# vsBenchPowerSupply.net
KiCad netlist of a schematic drawn in EAGLE
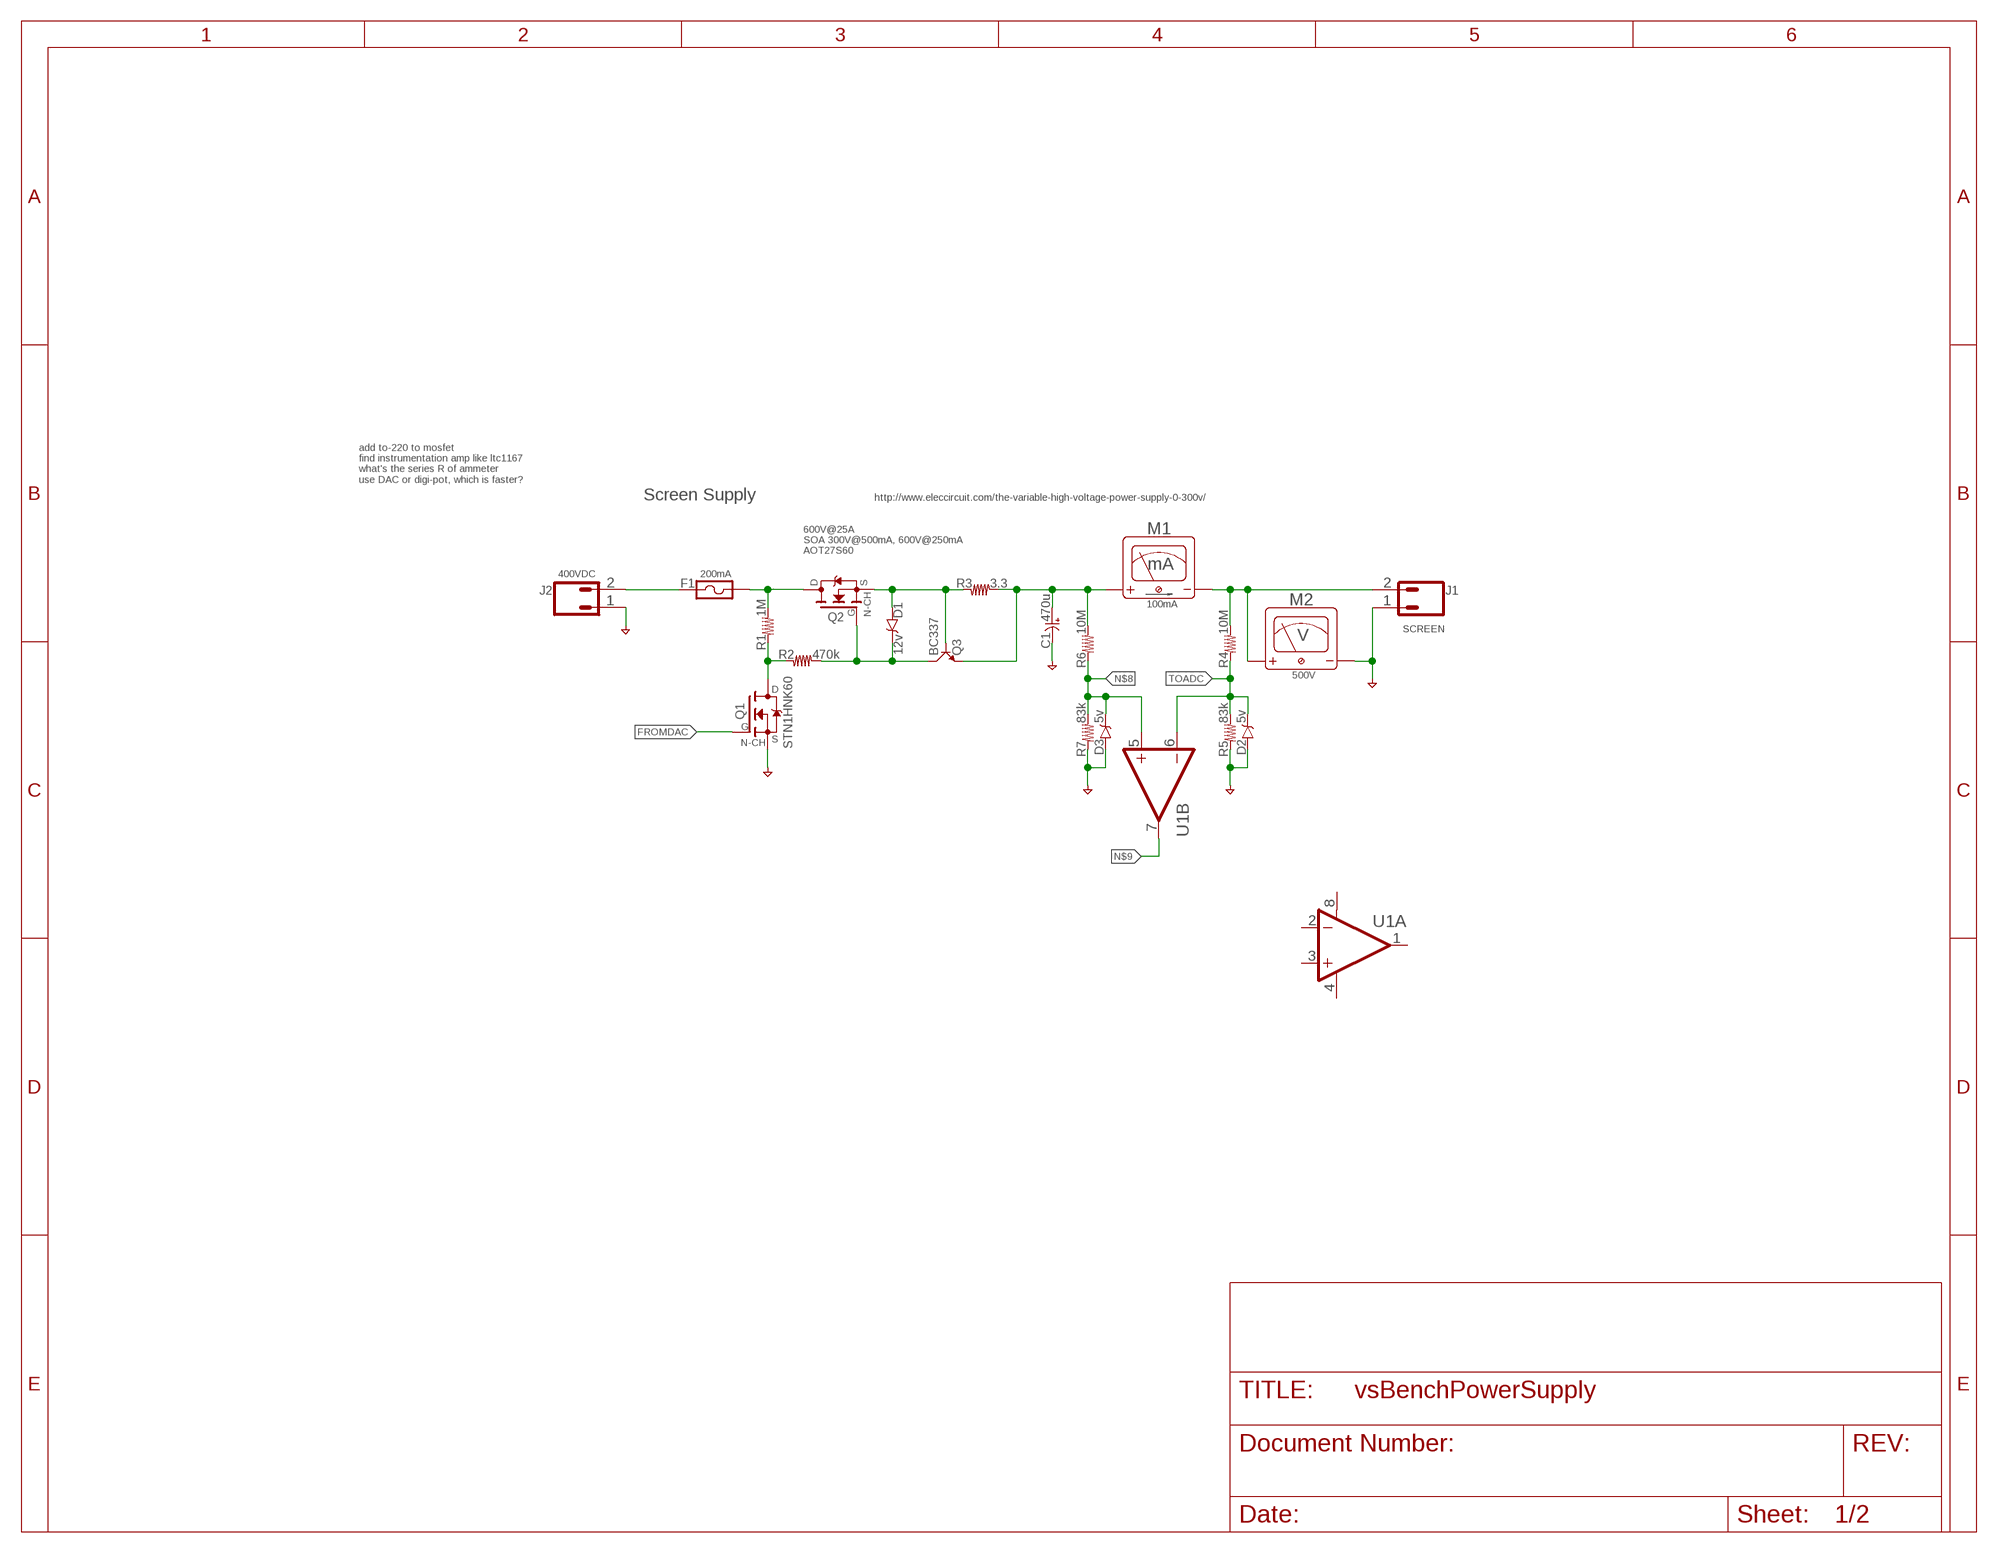
[diagram p0: schematic, sheet 1]
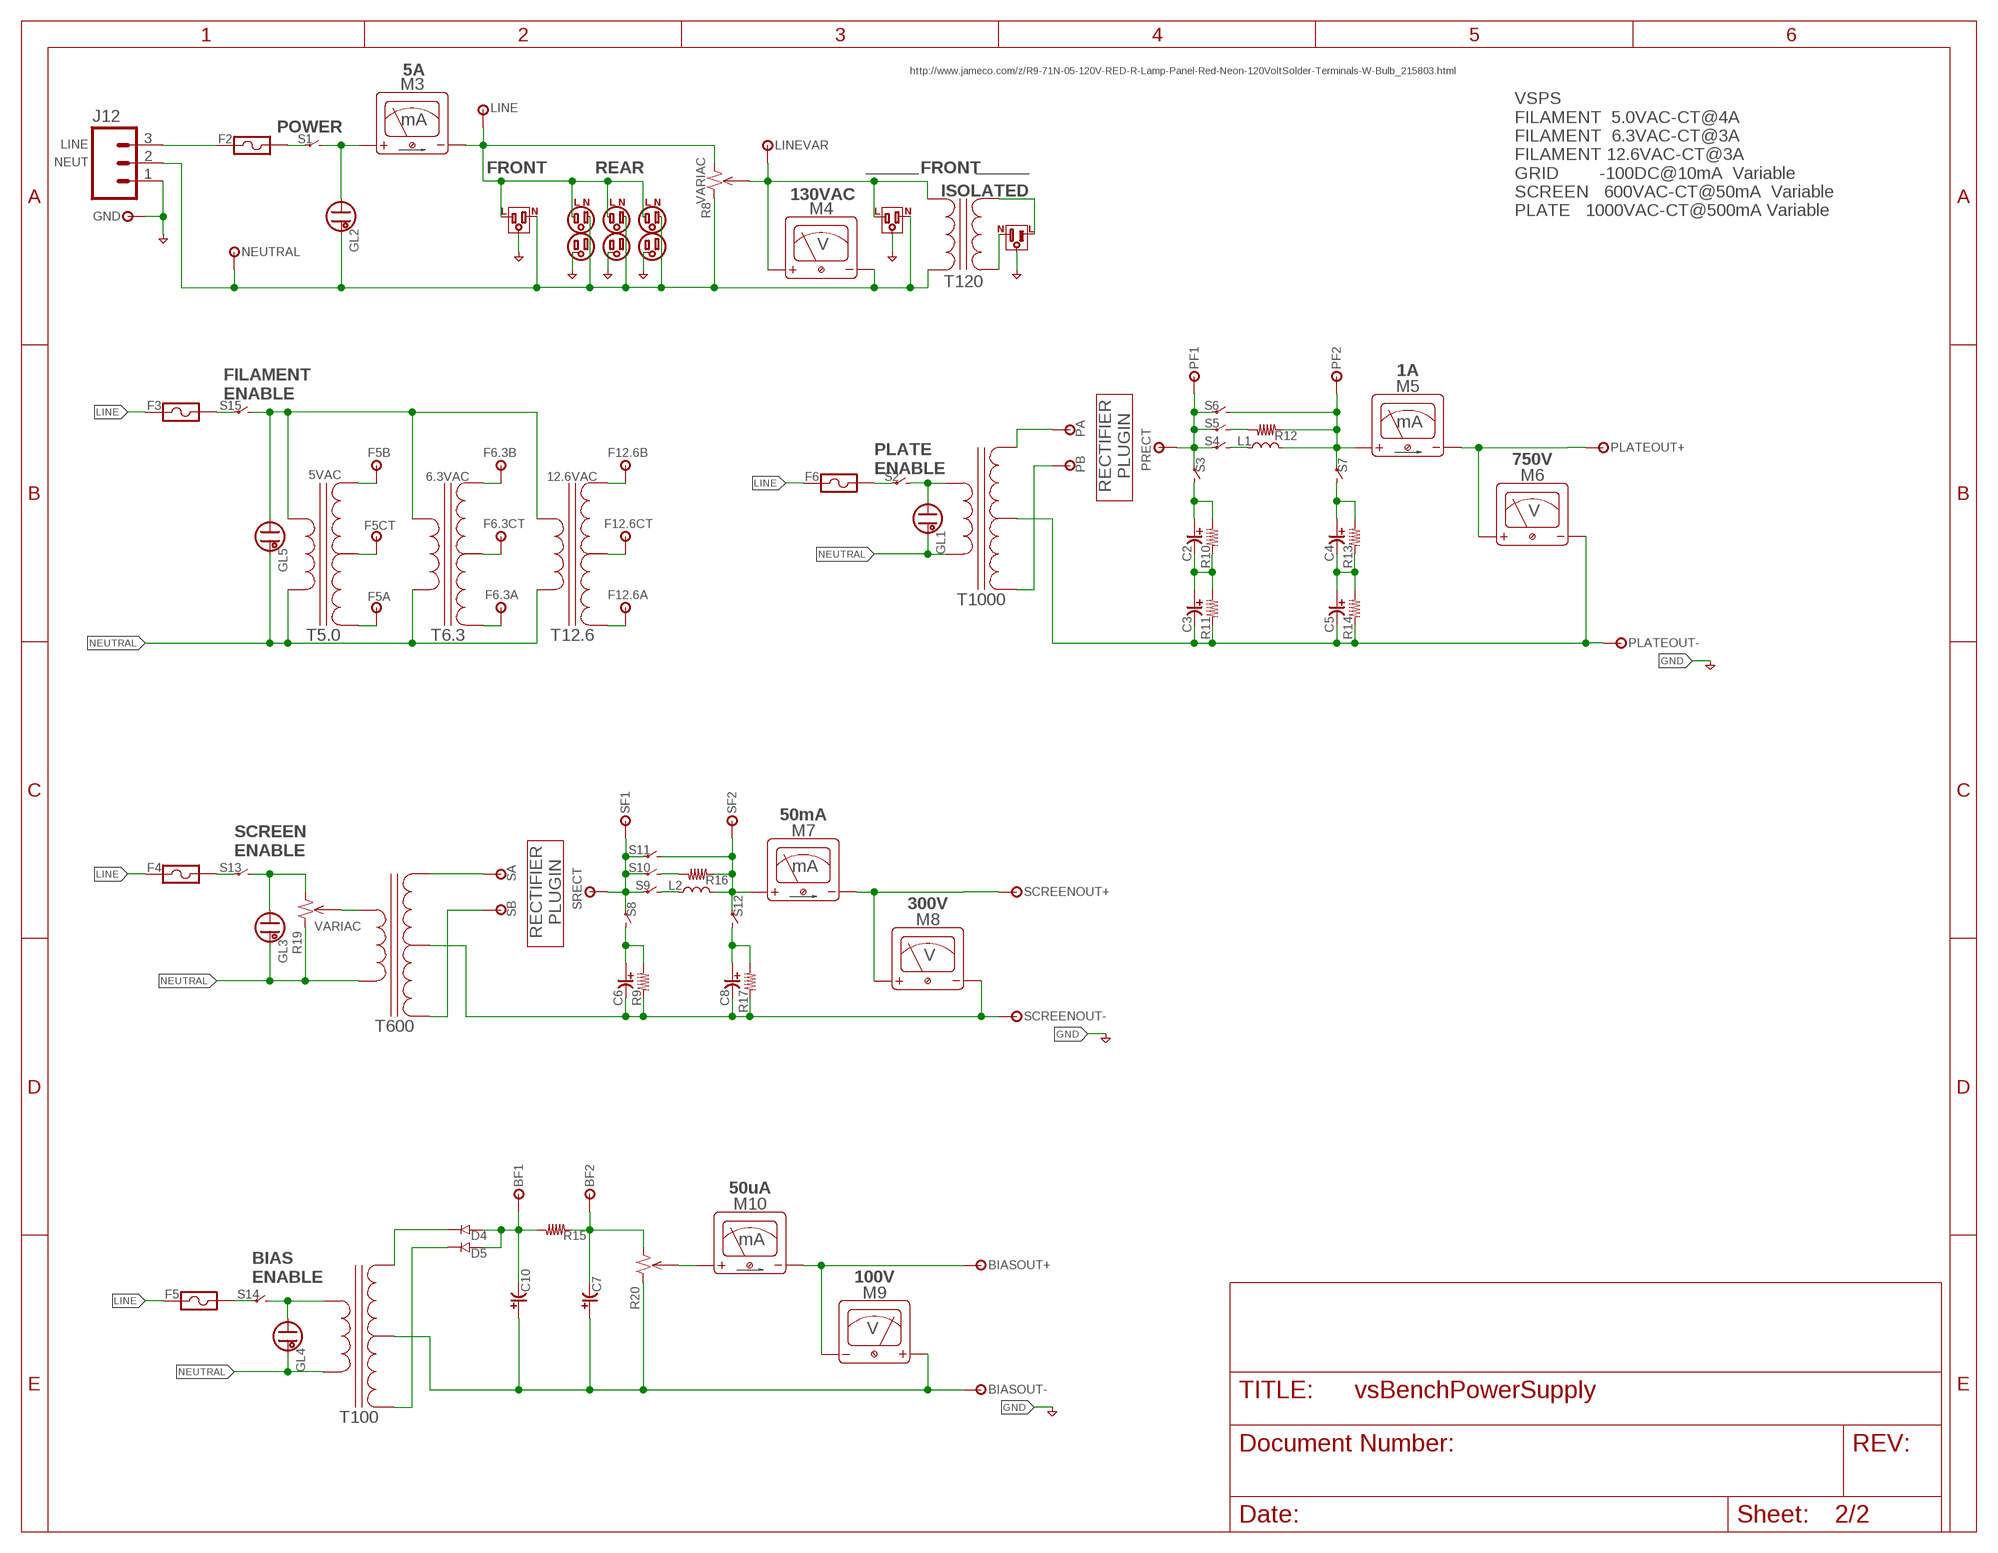
[diagram p1: schematic, sheet 2]

(export (version "E")
  (design (tool "Eeschema 10.0.6"))
  (components
    (comp (ref "C1")
      (value "470u")
      (footprint "eagle-import:E5-10,5")
      (libsource (lib "eagle-import") (part "C-E5-10.5"))
    )
    (comp (ref "D1")
      (value "12v")
      (footprint "eagle-import:SOD-323")
      (libsource (lib "eagle-import") (part "DIODE-ZENER-0805"))
    )
    (comp (ref "D2")
      (value "5v")
      (footprint "eagle-import:SOD-323")
      (libsource (lib "eagle-import") (part "DIODE-ZENER-0805"))
    )
    (comp (ref "D3")
      (value "5v")
      (footprint "eagle-import:SOD-323")
      (libsource (lib "eagle-import") (part "DIODE-ZENER-0805"))
    )
    (comp (ref "F1")
      (value "FUSE-HOLDER-3557-2")
      (footprint "eagle-import:3557-2")
      (libsource (lib "eagle-import") (part "FUSE-HOLDER-3557-2"))
    )
    (comp (ref "J1")
      (value "CONN-02-3.81MM-PLUGIN-SCREW")
      (footprint "eagle-import:CONN-3.81MM-KF2EDG-2")
      (libsource (lib "eagle-import") (part "CONN-02-3.81MM-PLUGIN-SCREW"))
    )
    (comp (ref "J2")
      (value "CONN-02-3.81MM-PLUGIN-SCREW")
      (footprint "eagle-import:CONN-3.81MM-KF2EDG-2")
      (libsource (lib "eagle-import") (part "CONN-02-3.81MM-PLUGIN-SCREW"))
    )
    (comp (ref "M1")
      (value "METER-PANEL-ANALOG-CURRENT-PLUGIN-3.81MM")
      (footprint "eagle-import:CONN-3.81MM-KF2EDG-2")
      (libsource (lib "eagle-import") (part "METER-PANEL-ANALOG-CURRENT-PLUGIN-3.81MM"))
    )
    (comp (ref "M2")
      (value "METER-PANEL-ANALOG-VOLTAGE-PLUGIN-3.81MM")
      (footprint "eagle-import:CONN-3.81MM-KF2EDG-2")
      (libsource (lib "eagle-import") (part "METER-PANEL-ANALOG-VOLTAGE-PLUGIN-3.81MM"))
    )
    (comp (ref "Q1")
      (value "STN1HNK60")
      (footprint "eagle-import:SOT23-3")
      (libsource (lib "eagle-import") (part "FET-NCH-SOT23"))
    )
    (comp (ref "Q2")
      (value "FET-NCH-TO252")
      (footprint "eagle-import:TO252")
      (libsource (lib "eagle-import") (part "FET-NCH-TO252"))
    )
    (comp (ref "Q3")
      (value "BC337")
      (footprint "eagle-import:SOT23-3")
      (libsource (lib "eagle-import") (part "TRANSISTOR_NPNSOT23-3"))
    )
    (comp (ref "R1")
      (value "1M")
      (footprint "eagle-import:R2512")
      (fields (field (name "DESC") "1W"))
      (libsource (lib "eagle-import") (part "R-2512"))
    )
    (comp (ref "R2")
      (value "470k")
      (footprint "eagle-import:R2512")
      (libsource (lib "eagle-import") (part "R-2512"))
    )
    (comp (ref "R3")
      (value "3.3")
      (footprint "eagle-import:R2512")
      (libsource (lib "eagle-import") (part "R-2512"))
    )
    (comp (ref "R4")
      (value "10M")
      (footprint "eagle-import:R2512")
      (fields (field (name "DESC") ".1%"))
      (libsource (lib "eagle-import") (part "R-2512"))
    )
    (comp (ref "R5")
      (value "83k")
      (footprint "eagle-import:R2512")
      (fields (field (name "DESC") ".1%"))
      (libsource (lib "eagle-import") (part "R-2512"))
    )
    (comp (ref "R6")
      (value "10M")
      (footprint "eagle-import:R2512")
      (fields (field (name "DESC") ",1%"))
      (libsource (lib "eagle-import") (part "R-2512"))
    )
    (comp (ref "R7")
      (value "83k")
      (footprint "eagle-import:R2512")
      (fields (field (name "DESC") ".1%"))
      (libsource (lib "eagle-import") (part "R-2512"))
    )
    (comp (ref "U1")
      (value "AMP-OPAMP-DUAL-SO08")
      (footprint "eagle-import:SO08")
      (libsource (lib "eagle-import") (part "AMP-OPAMP-DUAL-SO08"))
    )
    (comp (ref "BF1")
      (value "TESTPOINTTHRU")
      (footprint "eagle-import:TPTHRU")
      (libsource (lib "eagle-import") (part "TESTPOINTTHRU"))
    )
    (comp (ref "BF2")
      (value "TESTPOINTTHRU")
      (footprint "eagle-import:TPTHRU")
      (libsource (lib "eagle-import") (part "TESTPOINTTHRU"))
    )
    (comp (ref "BIASOUT+")
      (value "TESTPOINTTHRU")
      (footprint "eagle-import:TPTHRU")
      (libsource (lib "eagle-import") (part "TESTPOINTTHRU"))
    )
    (comp (ref "BIASOUT-")
      (value "TESTPOINTTHRU")
      (footprint "eagle-import:TPTHRU")
      (libsource (lib "eagle-import") (part "TESTPOINTTHRU"))
    )
    (comp (ref "C2")
      (value "C-POLARIZED-SMD-E-3MM")
      (footprint "eagle-import:E-3")
      (libsource (lib "eagle-import") (part "C-POLARIZED-SMD-E-3MM"))
    )
    (comp (ref "C3")
      (value "C-POLARIZED-SMD-E-3MM")
      (footprint "eagle-import:E-3")
      (libsource (lib "eagle-import") (part "C-POLARIZED-SMD-E-3MM"))
    )
    (comp (ref "C4")
      (value "C-POLARIZED-SMD-E-3MM")
      (footprint "eagle-import:E-3")
      (libsource (lib "eagle-import") (part "C-POLARIZED-SMD-E-3MM"))
    )
    (comp (ref "C5")
      (value "C-POLARIZED-SMD-E-3MM")
      (footprint "eagle-import:E-3")
      (libsource (lib "eagle-import") (part "C-POLARIZED-SMD-E-3MM"))
    )
    (comp (ref "C6")
      (value "C-POLARIZED-SMD-E-3MM")
      (footprint "eagle-import:E-3")
      (libsource (lib "eagle-import") (part "C-POLARIZED-SMD-E-3MM"))
    )
    (comp (ref "C7")
      (value "C-POLARIZED-SMD-E-3MM")
      (footprint "eagle-import:E-3")
      (libsource (lib "eagle-import") (part "C-POLARIZED-SMD-E-3MM"))
    )
    (comp (ref "C8")
      (value "C-POLARIZED-SMD-E-3MM")
      (footprint "eagle-import:E-3")
      (libsource (lib "eagle-import") (part "C-POLARIZED-SMD-E-3MM"))
    )
    (comp (ref "C10")
      (value "C-POLARIZED-SMD-E-3MM")
      (footprint "eagle-import:E-3")
      (libsource (lib "eagle-import") (part "C-POLARIZED-SMD-E-3MM"))
    )
    (comp (ref "D4")
      (value "DIODE-1N4148")
      (footprint "eagle-import:DO-35")
      (libsource (lib "eagle-import") (part "DIODE-1N4148"))
    )
    (comp (ref "D5")
      (value "DIODE-1N4148")
      (footprint "eagle-import:DO-35")
      (libsource (lib "eagle-import") (part "DIODE-1N4148"))
    )
    (comp (ref "F2")
      (value "FUSE-HOLDER-3557-2")
      (footprint "eagle-import:3557-2")
      (libsource (lib "eagle-import") (part "FUSE-HOLDER-3557-2"))
    )
    (comp (ref "F3")
      (value "FUSE-HOLDER-3557-2")
      (footprint "eagle-import:3557-2")
      (libsource (lib "eagle-import") (part "FUSE-HOLDER-3557-2"))
    )
    (comp (ref "F4")
      (value "FUSE-HOLDER-3557-2")
      (footprint "eagle-import:3557-2")
      (libsource (lib "eagle-import") (part "FUSE-HOLDER-3557-2"))
    )
    (comp (ref "F5")
      (value "FUSE-HOLDER-3557-2")
      (footprint "eagle-import:3557-2")
      (libsource (lib "eagle-import") (part "FUSE-HOLDER-3557-2"))
    )
    (comp (ref "F5A")
      (value "TESTPOINTTHRU")
      (footprint "eagle-import:TPTHRU")
      (libsource (lib "eagle-import") (part "TESTPOINTTHRU"))
    )
    (comp (ref "F5B")
      (value "TESTPOINTTHRU")
      (footprint "eagle-import:TPTHRU")
      (libsource (lib "eagle-import") (part "TESTPOINTTHRU"))
    )
    (comp (ref "F5CT")
      (value "TESTPOINTTHRU")
      (footprint "eagle-import:TPTHRU")
      (libsource (lib "eagle-import") (part "TESTPOINTTHRU"))
    )
    (comp (ref "F6")
      (value "FUSE-HOLDER-3557-2")
      (footprint "eagle-import:3557-2")
      (libsource (lib "eagle-import") (part "FUSE-HOLDER-3557-2"))
    )
    (comp (ref "F6.3A")
      (value "TESTPOINTTHRU")
      (footprint "eagle-import:TPTHRU")
      (libsource (lib "eagle-import") (part "TESTPOINTTHRU"))
    )
    (comp (ref "F6.3B")
      (value "TESTPOINTTHRU")
      (footprint "eagle-import:TPTHRU")
      (libsource (lib "eagle-import") (part "TESTPOINTTHRU"))
    )
    (comp (ref "F6.3CT")
      (value "TESTPOINTTHRU")
      (footprint "eagle-import:TPTHRU")
      (libsource (lib "eagle-import") (part "TESTPOINTTHRU"))
    )
    (comp (ref "F12.6A")
      (value "TESTPOINTTHRU")
      (footprint "eagle-import:TPTHRU")
      (libsource (lib "eagle-import") (part "TESTPOINTTHRU"))
    )
    (comp (ref "F12.6B")
      (value "TESTPOINTTHRU")
      (footprint "eagle-import:TPTHRU")
      (libsource (lib "eagle-import") (part "TESTPOINTTHRU"))
    )
    (comp (ref "F12.6CT")
      (value "TESTPOINTTHRU")
      (footprint "eagle-import:TPTHRU")
      (libsource (lib "eagle-import") (part "TESTPOINTTHRU"))
    )
    (comp (ref "GL1")
      (value "INDICATOR-NEON-BULB-NE2-DRILL")
      (footprint "eagle-import:NE2-NEON-BULB-DRILL")
      (libsource (lib "eagle-import") (part "INDICATOR-NEON-BULB-NE2-DRILL"))
    )
    (comp (ref "GL2")
      (value "INDICATOR-NEON-BULB-NE2-DRILL")
      (footprint "eagle-import:NE2-NEON-BULB-DRILL")
      (libsource (lib "eagle-import") (part "INDICATOR-NEON-BULB-NE2-DRILL"))
    )
    (comp (ref "GL3")
      (value "INDICATOR-NEON-BULB-NE2-DRILL")
      (footprint "eagle-import:NE2-NEON-BULB-DRILL")
      (libsource (lib "eagle-import") (part "INDICATOR-NEON-BULB-NE2-DRILL"))
    )
    (comp (ref "GL4")
      (value "INDICATOR-NEON-BULB-NE2-DRILL")
      (footprint "eagle-import:NE2-NEON-BULB-DRILL")
      (libsource (lib "eagle-import") (part "INDICATOR-NEON-BULB-NE2-DRILL"))
    )
    (comp (ref "GL5")
      (value "INDICATOR-NEON-BULB-NE2-DRILL")
      (footprint "eagle-import:NE2-NEON-BULB-DRILL")
      (libsource (lib "eagle-import") (part "INDICATOR-NEON-BULB-NE2-DRILL"))
    )
    (comp (ref "GND")
      (value "TESTPOINTTHRU")
      (footprint "eagle-import:TPTHRU")
      (libsource (lib "eagle-import") (part "TESTPOINTTHRU"))
    )
    (comp (ref "J3")
      (value "OUTLET-RECEPTABLE-SINGLE")
      (footprint "eagle-import:CONN-3.81MM-KF2EDG-3")
      (libsource (lib "eagle-import") (part "OUTLET-RECEPTABLE-SINGLE"))
    )
    (comp (ref "J4")
      (value "OUTLET-RECEPTABLE-SINGLE")
      (footprint "eagle-import:CONN-3.81MM-KF2EDG-3")
      (libsource (lib "eagle-import") (part "OUTLET-RECEPTABLE-SINGLE"))
    )
    (comp (ref "J5")
      (value "OUTLET-RECEPTABLE-SINGLE")
      (footprint "eagle-import:CONN-3.81MM-KF2EDG-3")
      (libsource (lib "eagle-import") (part "OUTLET-RECEPTABLE-SINGLE"))
    )
    (comp (ref "J12")
      (value "CONN-03-3.81MM-PLUGIN-SCREW")
      (footprint "eagle-import:CONN-3.81MM-KF2EDG-3")
      (libsource (lib "eagle-import") (part "CONN-03-3.81MM-PLUGIN-SCREW"))
    )
    (comp (ref "L1")
      (value "INDUCTOR-0805")
      (footprint "eagle-import:R0805")
      (libsource (lib "eagle-import") (part "INDUCTOR-0805"))
    )
    (comp (ref "L2")
      (value "INDUCTOR-0805")
      (footprint "eagle-import:R0805")
      (libsource (lib "eagle-import") (part "INDUCTOR-0805"))
    )
    (comp (ref "LINE")
      (value "TESTPOINTTHRU")
      (footprint "eagle-import:TPTHRU")
      (libsource (lib "eagle-import") (part "TESTPOINTTHRU"))
    )
    (comp (ref "LINEVAR")
      (value "TESTPOINTTHRU")
      (footprint "eagle-import:TPTHRU")
      (libsource (lib "eagle-import") (part "TESTPOINTTHRU"))
    )
    (comp (ref "M3")
      (value "METER-PANEL-ANALOG-CURRENT-PLUGIN-3.81MM")
      (footprint "eagle-import:CONN-3.81MM-KF2EDG-2")
      (libsource (lib "eagle-import") (part "METER-PANEL-ANALOG-CURRENT-PLUGIN-3.81MM"))
    )
    (comp (ref "M4")
      (value "METER-PANEL-ANALOG-VOLTAGE-PLUGIN-3.81MM")
      (footprint "eagle-import:CONN-3.81MM-KF2EDG-2")
      (libsource (lib "eagle-import") (part "METER-PANEL-ANALOG-VOLTAGE-PLUGIN-3.81MM"))
    )
    (comp (ref "M5")
      (value "METER-PANEL-ANALOG-CURRENT-PLUGIN-3.81MM")
      (footprint "eagle-import:CONN-3.81MM-KF2EDG-2")
      (libsource (lib "eagle-import") (part "METER-PANEL-ANALOG-CURRENT-PLUGIN-3.81MM"))
    )
    (comp (ref "M6")
      (value "METER-PANEL-ANALOG-VOLTAGE-PLUGIN-3.81MM")
      (footprint "eagle-import:CONN-3.81MM-KF2EDG-2")
      (libsource (lib "eagle-import") (part "METER-PANEL-ANALOG-VOLTAGE-PLUGIN-3.81MM"))
    )
    (comp (ref "M7")
      (value "METER-PANEL-ANALOG-CURRENT-PLUGIN-3.81MM")
      (footprint "eagle-import:CONN-3.81MM-KF2EDG-2")
      (libsource (lib "eagle-import") (part "METER-PANEL-ANALOG-CURRENT-PLUGIN-3.81MM"))
    )
    (comp (ref "M8")
      (value "METER-PANEL-ANALOG-VOLTAGE-PLUGIN-3.81MM")
      (footprint "eagle-import:CONN-3.81MM-KF2EDG-2")
      (libsource (lib "eagle-import") (part "METER-PANEL-ANALOG-VOLTAGE-PLUGIN-3.81MM"))
    )
    (comp (ref "M9")
      (value "METER-PANEL-ANALOG-VOLTAGE-PLUGIN-3.81MM")
      (footprint "eagle-import:CONN-3.81MM-KF2EDG-2")
      (libsource (lib "eagle-import") (part "METER-PANEL-ANALOG-VOLTAGE-PLUGIN-3.81MM"))
    )
    (comp (ref "M10")
      (value "METER-PANEL-ANALOG-CURRENT-PLUGIN-3.81MM")
      (footprint "eagle-import:CONN-3.81MM-KF2EDG-2")
      (libsource (lib "eagle-import") (part "METER-PANEL-ANALOG-CURRENT-PLUGIN-3.81MM"))
    )
    (comp (ref "NEUTRAL")
      (value "TESTPOINTTHRU")
      (footprint "eagle-import:TPTHRU")
      (libsource (lib "eagle-import") (part "TESTPOINTTHRU"))
    )
    (comp (ref "PA")
      (value "TESTPOINTTHRU")
      (footprint "eagle-import:TPTHRU")
      (libsource (lib "eagle-import") (part "TESTPOINTTHRU"))
    )
    (comp (ref "PB")
      (value "TESTPOINTTHRU")
      (footprint "eagle-import:TPTHRU")
      (libsource (lib "eagle-import") (part "TESTPOINTTHRU"))
    )
    (comp (ref "PF1")
      (value "TESTPOINTTHRU")
      (footprint "eagle-import:TPTHRU")
      (libsource (lib "eagle-import") (part "TESTPOINTTHRU"))
    )
    (comp (ref "PF2")
      (value "TESTPOINTTHRU")
      (footprint "eagle-import:TPTHRU")
      (libsource (lib "eagle-import") (part "TESTPOINTTHRU"))
    )
    (comp (ref "PLATEOUT+")
      (value "TESTPOINTTHRU")
      (footprint "eagle-import:TPTHRU")
      (libsource (lib "eagle-import") (part "TESTPOINTTHRU"))
    )
    (comp (ref "PLATEOUT-")
      (value "TESTPOINTTHRU")
      (footprint "eagle-import:TPTHRU")
      (libsource (lib "eagle-import") (part "TESTPOINTTHRU"))
    )
    (comp (ref "PRECT")
      (value "TESTPOINTTHRU")
      (footprint "eagle-import:TPTHRU")
      (libsource (lib "eagle-import") (part "TESTPOINTTHRU"))
    )
    (comp (ref "R8")
      (value "POTENTIOMETER")
      (footprint "eagle-import:CONN-.100-3")
      (libsource (lib "eagle-import") (part "POTENTIOMETER"))
    )
    (comp (ref "R9")
      (value "R-0402")
      (footprint "eagle-import:R0402")
      (libsource (lib "eagle-import") (part "R-0402"))
    )
    (comp (ref "R10")
      (value "R-0402")
      (footprint "eagle-import:R0402")
      (libsource (lib "eagle-import") (part "R-0402"))
    )
    (comp (ref "R11")
      (value "R-0402")
      (footprint "eagle-import:R0402")
      (libsource (lib "eagle-import") (part "R-0402"))
    )
    (comp (ref "R12")
      (value "R-0402")
      (footprint "eagle-import:R0402")
      (libsource (lib "eagle-import") (part "R-0402"))
    )
    (comp (ref "R13")
      (value "R-0402")
      (footprint "eagle-import:R0402")
      (libsource (lib "eagle-import") (part "R-0402"))
    )
    (comp (ref "R14")
      (value "R-0402")
      (footprint "eagle-import:R0402")
      (libsource (lib "eagle-import") (part "R-0402"))
    )
    (comp (ref "R15")
      (value "R-0402")
      (footprint "eagle-import:R0402")
      (libsource (lib "eagle-import") (part "R-0402"))
    )
    (comp (ref "R16")
      (value "R-0402")
      (footprint "eagle-import:R0402")
      (libsource (lib "eagle-import") (part "R-0402"))
    )
    (comp (ref "R17")
      (value "R-0402")
      (footprint "eagle-import:R0402")
      (libsource (lib "eagle-import") (part "R-0402"))
    )
    (comp (ref "R19")
      (value "POTENTIOMETER")
      (footprint "eagle-import:CONN-.100-3")
      (libsource (lib "eagle-import") (part "POTENTIOMETER"))
    )
    (comp (ref "R20")
      (value "POTENTIOMETER")
      (footprint "eagle-import:CONN-.100-3")
      (libsource (lib "eagle-import") (part "POTENTIOMETER"))
    )
    (comp (ref "S1")
      (value "SWITCH-PANEL-SPST")
      (footprint "eagle-import:CONN-.100-2")
      (libsource (lib "eagle-import") (part "SWITCH-PANEL-SPST"))
    )
    (comp (ref "S2")
      (value "SWITCH-PANEL-SPST")
      (footprint "eagle-import:CONN-.100-2")
      (libsource (lib "eagle-import") (part "SWITCH-PANEL-SPST"))
    )
    (comp (ref "S3")
      (value "SWITCH-PANEL-SPST")
      (footprint "eagle-import:CONN-.100-2")
      (libsource (lib "eagle-import") (part "SWITCH-PANEL-SPST"))
    )
    (comp (ref "S4")
      (value "SWITCH-PANEL-SPST")
      (footprint "eagle-import:CONN-.100-2")
      (libsource (lib "eagle-import") (part "SWITCH-PANEL-SPST"))
    )
    (comp (ref "S5")
      (value "SWITCH-PANEL-SPST")
      (footprint "eagle-import:CONN-.100-2")
      (libsource (lib "eagle-import") (part "SWITCH-PANEL-SPST"))
    )
    (comp (ref "S6")
      (value "SWITCH-PANEL-SPST")
      (footprint "eagle-import:CONN-.100-2")
      (libsource (lib "eagle-import") (part "SWITCH-PANEL-SPST"))
    )
    (comp (ref "S7")
      (value "SWITCH-PANEL-SPST")
      (footprint "eagle-import:CONN-.100-2")
      (libsource (lib "eagle-import") (part "SWITCH-PANEL-SPST"))
    )
    (comp (ref "S8")
      (value "SWITCH-PANEL-SPST")
      (footprint "eagle-import:CONN-.100-2")
      (libsource (lib "eagle-import") (part "SWITCH-PANEL-SPST"))
    )
    (comp (ref "S9")
      (value "SWITCH-PANEL-SPST")
      (footprint "eagle-import:CONN-.100-2")
      (libsource (lib "eagle-import") (part "SWITCH-PANEL-SPST"))
    )
    (comp (ref "S10")
      (value "SWITCH-PANEL-SPST")
      (footprint "eagle-import:CONN-.100-2")
      (libsource (lib "eagle-import") (part "SWITCH-PANEL-SPST"))
    )
    (comp (ref "S11")
      (value "SWITCH-PANEL-SPST")
      (footprint "eagle-import:CONN-.100-2")
      (libsource (lib "eagle-import") (part "SWITCH-PANEL-SPST"))
    )
    (comp (ref "S12")
      (value "SWITCH-PANEL-SPST")
      (footprint "eagle-import:CONN-.100-2")
      (libsource (lib "eagle-import") (part "SWITCH-PANEL-SPST"))
    )
    (comp (ref "S13")
      (value "SWITCH-PANEL-SPST")
      (footprint "eagle-import:CONN-.100-2")
      (libsource (lib "eagle-import") (part "SWITCH-PANEL-SPST"))
    )
    (comp (ref "S14")
      (value "SWITCH-PANEL-SPST")
      (footprint "eagle-import:CONN-.100-2")
      (libsource (lib "eagle-import") (part "SWITCH-PANEL-SPST"))
    )
    (comp (ref "S15")
      (value "SWITCH-PANEL-SPST")
      (footprint "eagle-import:CONN-.100-2")
      (libsource (lib "eagle-import") (part "SWITCH-PANEL-SPST"))
    )
    (comp (ref "SA")
      (value "TESTPOINTTHRU")
      (footprint "eagle-import:TPTHRU")
      (libsource (lib "eagle-import") (part "TESTPOINTTHRU"))
    )
    (comp (ref "SB")
      (value "TESTPOINTTHRU")
      (footprint "eagle-import:TPTHRU")
      (libsource (lib "eagle-import") (part "TESTPOINTTHRU"))
    )
    (comp (ref "SCREENOUT+")
      (value "TESTPOINTTHRU")
      (footprint "eagle-import:TPTHRU")
      (libsource (lib "eagle-import") (part "TESTPOINTTHRU"))
    )
    (comp (ref "SCREENOUT-")
      (value "TESTPOINTTHRU")
      (footprint "eagle-import:TPTHRU")
      (libsource (lib "eagle-import") (part "TESTPOINTTHRU"))
    )
    (comp (ref "SF1")
      (value "TESTPOINTTHRU")
      (footprint "eagle-import:TPTHRU")
      (libsource (lib "eagle-import") (part "TESTPOINTTHRU"))
    )
    (comp (ref "SF2")
      (value "TESTPOINTTHRU")
      (footprint "eagle-import:TPTHRU")
      (libsource (lib "eagle-import") (part "TESTPOINTTHRU"))
    )
    (comp (ref "SRECT")
      (value "TESTPOINTTHRU")
      (footprint "eagle-import:TPTHRU")
      (libsource (lib "eagle-import") (part "TESTPOINTTHRU"))
    )
    (comp (ref "T5.0")
      (value "TRANSFORMER-3-2")
      (footprint "eagle-import:CONN-.100-5")
      (libsource (lib "eagle-import") (part "TRANSFORMER-3-2"))
    )
    (comp (ref "T6.3")
      (value "TRANSFORMER-3-2")
      (footprint "eagle-import:CONN-.100-5")
      (libsource (lib "eagle-import") (part "TRANSFORMER-3-2"))
    )
    (comp (ref "T12.6")
      (value "TRANSFORMER-3-2")
      (footprint "eagle-import:CONN-.100-5")
      (libsource (lib "eagle-import") (part "TRANSFORMER-3-2"))
    )
    (comp (ref "T100")
      (value "TRANSFORMER-3-2")
      (footprint "eagle-import:CONN-.100-5")
      (libsource (lib "eagle-import") (part "TRANSFORMER-3-2"))
    )
    (comp (ref "T120")
      (value "TRANSFORMER-2-2")
      (footprint "eagle-import:TRANSFORMER-4-2-G")
      (libsource (lib "eagle-import") (part "TRANSFORMER-2-2"))
    )
    (comp (ref "T600")
      (value "TRANSFORMER-3-2")
      (footprint "eagle-import:CONN-.100-5")
      (libsource (lib "eagle-import") (part "TRANSFORMER-3-2"))
    )
    (comp (ref "T1000")
      (value "TRANSFORMER-3-2")
      (footprint "eagle-import:CONN-.100-5")
      (libsource (lib "eagle-import") (part "TRANSFORMER-3-2"))
    )
    (comp (ref "U$1")
      (value "OUTLET-RECEPTACLE")
      (footprint "eagle-import:CONN-3.81MM-KF2EDG-3")
      (libsource (lib "eagle-import") (part "OUTLET-RECEPTACLE"))
    )
    (comp (ref "U$2")
      (value "OUTLET-RECEPTACLE")
      (footprint "eagle-import:CONN-3.81MM-KF2EDG-3")
      (libsource (lib "eagle-import") (part "OUTLET-RECEPTACLE"))
    )
    (comp (ref "U$3")
      (value "OUTLET-RECEPTACLE")
      (footprint "eagle-import:CONN-3.81MM-KF2EDG-3")
      (libsource (lib "eagle-import") (part "OUTLET-RECEPTACLE"))
    )
  )
  (nets
    (net (code "1") (name "FROMDAC") (class "Default")
      (node (ref "Q1") (pin "1") (pinfunction "G_1") (pintype "passive"))
    )
    (net (code "2") (name "GND") (class "Default")
      (node (ref "C1") (pin "-") (pinfunction "2_-") (pintype "passive"))
      (node (ref "D2") (pin "A") (pinfunction "A_A") (pintype "passive"))
      (node (ref "D3") (pin "A") (pinfunction "A_A") (pintype "passive"))
      (node (ref "GND") (pin "1") (pinfunction "P$1_1") (pintype "bidirectional"))
      (node (ref "J1") (pin "1") (pinfunction "1_1") (pintype "passive"))
      (node (ref "J12") (pin "1") (pinfunction "1_1") (pintype "passive"))
      (node (ref "J2") (pin "1") (pinfunction "1_1") (pintype "passive"))
      (node (ref "J3") (pin "1") (pinfunction "GND_1") (pintype "bidirectional"))
      (node (ref "J4") (pin "1") (pinfunction "GND_1") (pintype "bidirectional"))
      (node (ref "J5") (pin "1") (pinfunction "GND_1") (pintype "bidirectional"))
      (node (ref "M2") (pin "1") (pinfunction "-_1") (pintype "bidirectional"))
      (node (ref "Q1") (pin "2") (pinfunction "S_2") (pintype "passive"))
      (node (ref "R5") (pin "1") (pinfunction "1_1") (pintype "passive"))
      (node (ref "R7") (pin "1") (pinfunction "1_1") (pintype "passive"))
      (node (ref "U$1") (pin "1") (pinfunction "GND_1") (pintype "bidirectional"))
      (node (ref "U$2") (pin "1") (pinfunction "GND_1") (pintype "bidirectional"))
      (node (ref "U$3") (pin "1") (pinfunction "GND_1") (pintype "bidirectional"))
    )
    (net (code "3") (name "LINE") (class "Default")
      (node (ref "F3") (pin "1@1") (pinfunction "P$1_1@1") (pintype "bidirectional"))
      (node (ref "F3") (pin "1@2") (pinfunction "P$1_1@2") (pintype "bidirectional"))
      (node (ref "F4") (pin "1@1") (pinfunction "P$1_1@1") (pintype "bidirectional"))
      (node (ref "F4") (pin "1@2") (pinfunction "P$1_1@2") (pintype "bidirectional"))
      (node (ref "F5") (pin "1@1") (pinfunction "P$1_1@1") (pintype "bidirectional"))
      (node (ref "F5") (pin "1@2") (pinfunction "P$1_1@2") (pintype "bidirectional"))
      (node (ref "F6") (pin "1@1") (pinfunction "P$1_1@1") (pintype "bidirectional"))
      (node (ref "F6") (pin "1@2") (pinfunction "P$1_1@2") (pintype "bidirectional"))
      (node (ref "J3") (pin "3") (pinfunction "LINE_3") (pintype "bidirectional"))
      (node (ref "LINE") (pin "1") (pinfunction "P$1_1") (pintype "bidirectional"))
      (node (ref "M3") (pin "1") (pinfunction "-_1") (pintype "bidirectional"))
      (node (ref "R8") (pin "3") (pinfunction "2_3") (pintype "passive"))
      (node (ref "U$1") (pin "3") (pinfunction "LINE_3") (pintype "bidirectional"))
      (node (ref "U$2") (pin "3") (pinfunction "LINE_3") (pintype "bidirectional"))
      (node (ref "U$3") (pin "3") (pinfunction "LINE_3") (pintype "bidirectional"))
    )
    (net (code "4") (name "N$8") (class "Default")
      (node (ref "D3") (pin "C") (pinfunction "C_C") (pintype "passive"))
      (node (ref "R6") (pin "1") (pinfunction "1_1") (pintype "passive"))
      (node (ref "R7") (pin "2") (pinfunction "2_2") (pintype "passive"))
      (node (ref "U1") (pin "5") (pinfunction "+IN_5") (pintype "input"))
    )
    (net (code "5") (name "N$9") (class "Default")
      (node (ref "U1") (pin "7") (pinfunction "OUT_7") (pintype "output"))
    )
    (net (code "6") (name "NEUTRAL") (class "Default")
      (node (ref "GL1") (pin "2") (pinfunction "A1_2") (pintype "passive"))
      (node (ref "GL2") (pin "2") (pinfunction "A1_2") (pintype "passive"))
      (node (ref "GL3") (pin "2") (pinfunction "A1_2") (pintype "passive"))
      (node (ref "GL4") (pin "2") (pinfunction "A1_2") (pintype "passive"))
      (node (ref "GL5") (pin "2") (pinfunction "A1_2") (pintype "passive"))
      (node (ref "J12") (pin "2") (pinfunction "2_2") (pintype "passive"))
      (node (ref "J3") (pin "2") (pinfunction "NEU_2") (pintype "bidirectional"))
      (node (ref "J5") (pin "2") (pinfunction "NEU_2") (pintype "bidirectional"))
      (node (ref "M4") (pin "1") (pinfunction "-_1") (pintype "bidirectional"))
      (node (ref "NEUTRAL") (pin "1") (pinfunction "P$1_1") (pintype "bidirectional"))
      (node (ref "R19") (pin "1") (pinfunction "1_1") (pintype "passive"))
      (node (ref "R8") (pin "1") (pinfunction "1_1") (pintype "passive"))
      (node (ref "T100") (pin "2") (pinfunction "S2_2") (pintype "passive"))
      (node (ref "T1000") (pin "2") (pinfunction "S2_2") (pintype "passive"))
      (node (ref "T12.6") (pin "2") (pinfunction "S2_2") (pintype "passive"))
      (node (ref "T120") (pin "2") (pinfunction "P2_2") (pintype "passive"))
      (node (ref "T5.0") (pin "2") (pinfunction "S2_2") (pintype "passive"))
      (node (ref "T6.3") (pin "2") (pinfunction "S2_2") (pintype "passive"))
      (node (ref "T600") (pin "2") (pinfunction "S2_2") (pintype "passive"))
      (node (ref "U$1") (pin "2") (pinfunction "NEU_2") (pintype "bidirectional"))
      (node (ref "U$2") (pin "2") (pinfunction "NEU_2") (pintype "bidirectional"))
      (node (ref "U$3") (pin "2") (pinfunction "NEU_2") (pintype "bidirectional"))
    )
    (net (code "7") (name "Net-(BF1-P$1)") (class "Default")
      (node (ref "BF1") (pin "1") (pinfunction "P$1_1") (pintype "bidirectional"))
      (node (ref "C10") (pin "-") (pinfunction "-_-") (pintype "passive"))
      (node (ref "D4") (pin "A") (pinfunction "A_A") (pintype "bidirectional"))
      (node (ref "D5") (pin "A") (pinfunction "A_A") (pintype "bidirectional"))
      (node (ref "R15") (pin "2") (pinfunction "2_2") (pintype "passive"))
    )
    (net (code "8") (name "Net-(BF2-P$1)") (class "Default")
      (node (ref "BF2") (pin "1") (pinfunction "P$1_1") (pintype "bidirectional"))
      (node (ref "C7") (pin "-") (pinfunction "-_-") (pintype "passive"))
      (node (ref "R15") (pin "1") (pinfunction "1_1") (pintype "passive"))
      (node (ref "R20") (pin "3") (pinfunction "2_3") (pintype "passive"))
    )
    (net (code "9") (name "Net-(BIASOUT+-P$1)") (class "Default")
      (node (ref "BIASOUT+") (pin "1") (pinfunction "P$1_1") (pintype "bidirectional"))
      (node (ref "M10") (pin "1") (pinfunction "-_1") (pintype "bidirectional"))
      (node (ref "M9") (pin "1") (pinfunction "-_1") (pintype "bidirectional"))
    )
    (net (code "10") (name "Net-(BIASOUT--P$1)") (class "Default")
      (node (ref "BIASOUT-") (pin "1") (pinfunction "P$1_1") (pintype "bidirectional"))
      (node (ref "C10") (pin "+") (pinfunction "+_+") (pintype "passive"))
      (node (ref "C7") (pin "+") (pinfunction "+_+") (pintype "passive"))
      (node (ref "M9") (pin "2") (pinfunction "+_2") (pintype "bidirectional"))
      (node (ref "R20") (pin "1") (pinfunction "1_1") (pintype "passive"))
      (node (ref "T100") (pin "4") (pinfunction "PCT_4") (pintype "passive"))
    )
    (net (code "11") (name "Net-(C1-1)") (class "Default")
      (node (ref "C1") (pin "+") (pinfunction "1_+") (pintype "passive"))
      (node (ref "M1") (pin "2") (pinfunction "+_2") (pintype "bidirectional"))
      (node (ref "Q3") (pin "2") (pinfunction "E_2") (pintype "passive"))
      (node (ref "R3") (pin "2") (pinfunction "2_2") (pintype "passive"))
      (node (ref "R6") (pin "2") (pinfunction "2_2") (pintype "passive"))
    )
    (net (code "12") (name "Net-(C2-Pad+)") (class "Default")
      (node (ref "C2") (pin "+") (pinfunction "+_+") (pintype "passive"))
      (node (ref "R10") (pin "2") (pinfunction "2_2") (pintype "passive"))
      (node (ref "S3") (pin "2") (pinfunction "2_2") (pintype "passive"))
    )
    (net (code "13") (name "Net-(C2-Pad-)") (class "Default")
      (node (ref "C2") (pin "-") (pinfunction "-_-") (pintype "passive"))
      (node (ref "C3") (pin "+") (pinfunction "+_+") (pintype "passive"))
      (node (ref "R10") (pin "1") (pinfunction "1_1") (pintype "passive"))
      (node (ref "R11") (pin "2") (pinfunction "2_2") (pintype "passive"))
    )
    (net (code "14") (name "Net-(C4-Pad+)") (class "Default")
      (node (ref "C4") (pin "+") (pinfunction "+_+") (pintype "passive"))
      (node (ref "R13") (pin "2") (pinfunction "2_2") (pintype "passive"))
      (node (ref "S7") (pin "2") (pinfunction "2_2") (pintype "passive"))
    )
    (net (code "15") (name "Net-(C4-Pad-)") (class "Default")
      (node (ref "C4") (pin "-") (pinfunction "-_-") (pintype "passive"))
      (node (ref "C5") (pin "+") (pinfunction "+_+") (pintype "passive"))
      (node (ref "R13") (pin "1") (pinfunction "1_1") (pintype "passive"))
      (node (ref "R14") (pin "2") (pinfunction "2_2") (pintype "passive"))
    )
    (net (code "16") (name "Net-(C6-Pad+)") (class "Default")
      (node (ref "C6") (pin "+") (pinfunction "+_+") (pintype "passive"))
      (node (ref "R9") (pin "2") (pinfunction "2_2") (pintype "passive"))
      (node (ref "S8") (pin "2") (pinfunction "2_2") (pintype "passive"))
    )
    (net (code "17") (name "Net-(C8-Pad+)") (class "Default")
      (node (ref "C8") (pin "+") (pinfunction "+_+") (pintype "passive"))
      (node (ref "R17") (pin "2") (pinfunction "2_2") (pintype "passive"))
      (node (ref "S12") (pin "2") (pinfunction "2_2") (pintype "passive"))
    )
    (net (code "18") (name "Net-(F1-P$1-Pad1@1)") (class "Default")
      (node (ref "F1") (pin "1@1") (pinfunction "P$1_1@1") (pintype "bidirectional"))
      (node (ref "F1") (pin "1@2") (pinfunction "P$1_1@2") (pintype "bidirectional"))
      (node (ref "J2") (pin "2") (pinfunction "2_2") (pintype "passive"))
    )
    (net (code "19") (name "Net-(F2-P$1-Pad1@1)") (class "Default")
      (node (ref "F2") (pin "1@1") (pinfunction "P$1_1@1") (pintype "bidirectional"))
      (node (ref "F2") (pin "1@2") (pinfunction "P$1_1@2") (pintype "bidirectional"))
      (node (ref "J12") (pin "3") (pinfunction "3_3") (pintype "passive"))
    )
    (net (code "20") (name "Net-(F2-P$2-Pad2@1)") (class "Default")
      (node (ref "F2") (pin "2@1") (pinfunction "P$2_2@1") (pintype "bidirectional"))
      (node (ref "F2") (pin "2@2") (pinfunction "P$2_2@2") (pintype "bidirectional"))
      (node (ref "S1") (pin "1") (pinfunction "1_1") (pintype "passive"))
    )
    (net (code "21") (name "Net-(F3-P$2-Pad2@1)") (class "Default")
      (node (ref "F3") (pin "2@1") (pinfunction "P$2_2@1") (pintype "bidirectional"))
      (node (ref "F3") (pin "2@2") (pinfunction "P$2_2@2") (pintype "bidirectional"))
      (node (ref "S15") (pin "1") (pinfunction "1_1") (pintype "passive"))
    )
    (net (code "22") (name "Net-(F4-P$2-Pad2@1)") (class "Default")
      (node (ref "F4") (pin "2@1") (pinfunction "P$2_2@1") (pintype "bidirectional"))
      (node (ref "F4") (pin "2@2") (pinfunction "P$2_2@2") (pintype "bidirectional"))
      (node (ref "S13") (pin "1") (pinfunction "1_1") (pintype "passive"))
    )
    (net (code "23") (name "Net-(F5-P$2-Pad2@1)") (class "Default")
      (node (ref "F5") (pin "2@1") (pinfunction "P$2_2@1") (pintype "bidirectional"))
      (node (ref "F5") (pin "2@2") (pinfunction "P$2_2@2") (pintype "bidirectional"))
      (node (ref "S14") (pin "1") (pinfunction "1_1") (pintype "passive"))
    )
    (net (code "24") (name "Net-(F5A-P$1)") (class "Default")
      (node (ref "F5A") (pin "1") (pinfunction "P$1_1") (pintype "bidirectional"))
      (node (ref "T5.0") (pin "5") (pinfunction "P2_5") (pintype "passive"))
    )
    (net (code "25") (name "Net-(F5B-P$1)") (class "Default")
      (node (ref "F5B") (pin "1") (pinfunction "P$1_1") (pintype "bidirectional"))
      (node (ref "T5.0") (pin "3") (pinfunction "P1_3") (pintype "passive"))
    )
    (net (code "26") (name "Net-(F5CT-P$1)") (class "Default")
      (node (ref "F5CT") (pin "1") (pinfunction "P$1_1") (pintype "bidirectional"))
      (node (ref "T5.0") (pin "4") (pinfunction "PCT_4") (pintype "passive"))
    )
    (net (code "27") (name "Net-(F6-P$2-Pad2@1)") (class "Default")
      (node (ref "F6") (pin "2@1") (pinfunction "P$2_2@1") (pintype "bidirectional"))
      (node (ref "F6") (pin "2@2") (pinfunction "P$2_2@2") (pintype "bidirectional"))
      (node (ref "S2") (pin "1") (pinfunction "1_1") (pintype "passive"))
    )
    (net (code "28") (name "Net-(F6.3A-P$1)") (class "Default")
      (node (ref "F6.3A") (pin "1") (pinfunction "P$1_1") (pintype "bidirectional"))
      (node (ref "T6.3") (pin "5") (pinfunction "P2_5") (pintype "passive"))
    )
    (net (code "29") (name "Net-(F6.3B-P$1)") (class "Default")
      (node (ref "F6.3B") (pin "1") (pinfunction "P$1_1") (pintype "bidirectional"))
      (node (ref "T6.3") (pin "3") (pinfunction "P1_3") (pintype "passive"))
    )
    (net (code "30") (name "Net-(F6.3CT-P$1)") (class "Default")
      (node (ref "F6.3CT") (pin "1") (pinfunction "P$1_1") (pintype "bidirectional"))
      (node (ref "T6.3") (pin "4") (pinfunction "PCT_4") (pintype "passive"))
    )
    (net (code "31") (name "Net-(F12.6A-P$1)") (class "Default")
      (node (ref "F12.6A") (pin "1") (pinfunction "P$1_1") (pintype "bidirectional"))
      (node (ref "T12.6") (pin "5") (pinfunction "P2_5") (pintype "passive"))
    )
    (net (code "32") (name "Net-(F12.6B-P$1)") (class "Default")
      (node (ref "F12.6B") (pin "1") (pinfunction "P$1_1") (pintype "bidirectional"))
      (node (ref "T12.6") (pin "3") (pinfunction "P1_3") (pintype "passive"))
    )
    (net (code "33") (name "Net-(F12.6CT-P$1)") (class "Default")
      (node (ref "F12.6CT") (pin "1") (pinfunction "P$1_1") (pintype "bidirectional"))
      (node (ref "T12.6") (pin "4") (pinfunction "PCT_4") (pintype "passive"))
    )
    (net (code "34") (name "Net-(GL1-A)") (class "Default")
      (node (ref "GL1") (pin "1") (pinfunction "A_1") (pintype "passive"))
      (node (ref "S2") (pin "2") (pinfunction "2_2") (pintype "passive"))
      (node (ref "T1000") (pin "1") (pinfunction "S1_1") (pintype "passive"))
    )
    (net (code "35") (name "Net-(GL2-A)") (class "Default")
      (node (ref "GL2") (pin "1") (pinfunction "A_1") (pintype "passive"))
      (node (ref "M3") (pin "2") (pinfunction "+_2") (pintype "bidirectional"))
      (node (ref "S1") (pin "2") (pinfunction "2_2") (pintype "passive"))
    )
    (net (code "36") (name "Net-(GL3-A)") (class "Default")
      (node (ref "GL3") (pin "1") (pinfunction "A_1") (pintype "passive"))
      (node (ref "R19") (pin "3") (pinfunction "2_3") (pintype "passive"))
      (node (ref "S13") (pin "2") (pinfunction "2_2") (pintype "passive"))
    )
    (net (code "37") (name "Net-(GL4-A)") (class "Default")
      (node (ref "GL4") (pin "1") (pinfunction "A_1") (pintype "passive"))
      (node (ref "S14") (pin "2") (pinfunction "2_2") (pintype "passive"))
      (node (ref "T100") (pin "1") (pinfunction "S1_1") (pintype "passive"))
    )
    (net (code "38") (name "Net-(GL5-A)") (class "Default")
      (node (ref "GL5") (pin "1") (pinfunction "A_1") (pintype "passive"))
      (node (ref "S15") (pin "2") (pinfunction "2_2") (pintype "passive"))
      (node (ref "T12.6") (pin "1") (pinfunction "S1_1") (pintype "passive"))
      (node (ref "T5.0") (pin "1") (pinfunction "S1_1") (pintype "passive"))
      (node (ref "T6.3") (pin "1") (pinfunction "S1_1") (pintype "passive"))
    )
    (net (code "39") (name "Net-(J4-LINE)") (class "Default")
      (node (ref "J4") (pin "3") (pinfunction "LINE_3") (pintype "bidirectional"))
      (node (ref "T120") (pin "5") (pinfunction "S1_5") (pintype "passive"))
    )
    (net (code "40") (name "Net-(J4-NEU)") (class "Default")
      (node (ref "J4") (pin "2") (pinfunction "NEU_2") (pintype "bidirectional"))
      (node (ref "T120") (pin "6") (pinfunction "S2_6") (pintype "passive"))
    )
    (net (code "41") (name "Net-(J5-LINE)") (class "Default")
      (node (ref "J5") (pin "3") (pinfunction "LINE_3") (pintype "bidirectional"))
      (node (ref "LINEVAR") (pin "1") (pinfunction "P$1_1") (pintype "bidirectional"))
      (node (ref "M4") (pin "2") (pinfunction "+_2") (pintype "bidirectional"))
      (node (ref "R8") (pin "2") (pinfunction "W_2") (pintype "passive"))
      (node (ref "T120") (pin "1") (pinfunction "P1_1") (pintype "passive"))
    )
    (net (code "42") (name "Net-(L1-P$1)") (class "Default")
      (node (ref "L1") (pin "1") (pinfunction "P$1_1") (pintype "passive"))
      (node (ref "M5") (pin "2") (pinfunction "+_2") (pintype "bidirectional"))
      (node (ref "PF2") (pin "1") (pinfunction "P$1_1") (pintype "bidirectional"))
      (node (ref "R12") (pin "1") (pinfunction "1_1") (pintype "passive"))
      (node (ref "S6") (pin "2") (pinfunction "2_2") (pintype "passive"))
      (node (ref "S7") (pin "1") (pinfunction "1_1") (pintype "passive"))
    )
    (net (code "43") (name "Net-(L1-P$2)") (class "Default")
      (node (ref "L1") (pin "2") (pinfunction "P$2_2") (pintype "passive"))
      (node (ref "S4") (pin "2") (pinfunction "2_2") (pintype "passive"))
    )
    (net (code "44") (name "Net-(L2-P$1)") (class "Default")
      (node (ref "L2") (pin "1") (pinfunction "P$1_1") (pintype "passive"))
      (node (ref "M7") (pin "2") (pinfunction "+_2") (pintype "bidirectional"))
      (node (ref "R16") (pin "1") (pinfunction "1_1") (pintype "passive"))
      (node (ref "S11") (pin "2") (pinfunction "2_2") (pintype "passive"))
      (node (ref "S12") (pin "1") (pinfunction "1_1") (pintype "passive"))
      (node (ref "SF2") (pin "1") (pinfunction "P$1_1") (pintype "bidirectional"))
    )
    (net (code "45") (name "Net-(L2-P$2)") (class "Default")
      (node (ref "L2") (pin "2") (pinfunction "P$2_2") (pintype "passive"))
      (node (ref "S9") (pin "2") (pinfunction "2_2") (pintype "passive"))
    )
    (net (code "46") (name "Net-(M1--)") (class "Default")
      (node (ref "J1") (pin "2") (pinfunction "2_2") (pintype "passive"))
      (node (ref "M1") (pin "1") (pinfunction "-_1") (pintype "bidirectional"))
      (node (ref "M2") (pin "2") (pinfunction "+_2") (pintype "bidirectional"))
      (node (ref "R4") (pin "2") (pinfunction "2_2") (pintype "passive"))
    )
    (net (code "47") (name "Net-(M5--)") (class "Default")
      (node (ref "M5") (pin "1") (pinfunction "-_1") (pintype "bidirectional"))
      (node (ref "M6") (pin "2") (pinfunction "+_2") (pintype "bidirectional"))
      (node (ref "PLATEOUT+") (pin "1") (pinfunction "P$1_1") (pintype "bidirectional"))
    )
    (net (code "48") (name "Net-(M6--)") (class "Default")
      (node (ref "C3") (pin "-") (pinfunction "-_-") (pintype "passive"))
      (node (ref "C5") (pin "-") (pinfunction "-_-") (pintype "passive"))
      (node (ref "M6") (pin "1") (pinfunction "-_1") (pintype "bidirectional"))
      (node (ref "PLATEOUT-") (pin "1") (pinfunction "P$1_1") (pintype "bidirectional"))
      (node (ref "R11") (pin "1") (pinfunction "1_1") (pintype "passive"))
      (node (ref "R14") (pin "1") (pinfunction "1_1") (pintype "passive"))
      (node (ref "T1000") (pin "4") (pinfunction "PCT_4") (pintype "passive"))
    )
    (net (code "49") (name "Net-(M7--)") (class "Default")
      (node (ref "M7") (pin "1") (pinfunction "-_1") (pintype "bidirectional"))
      (node (ref "M8") (pin "2") (pinfunction "+_2") (pintype "bidirectional"))
      (node (ref "SCREENOUT+") (pin "1") (pinfunction "P$1_1") (pintype "bidirectional"))
    )
    (net (code "50") (name "Net-(M8--)") (class "Default")
      (node (ref "C6") (pin "-") (pinfunction "-_-") (pintype "passive"))
      (node (ref "C8") (pin "-") (pinfunction "-_-") (pintype "passive"))
      (node (ref "M8") (pin "1") (pinfunction "-_1") (pintype "bidirectional"))
      (node (ref "R17") (pin "1") (pinfunction "1_1") (pintype "passive"))
      (node (ref "R9") (pin "1") (pinfunction "1_1") (pintype "passive"))
      (node (ref "SCREENOUT-") (pin "1") (pinfunction "P$1_1") (pintype "bidirectional"))
      (node (ref "T600") (pin "4") (pinfunction "PCT_4") (pintype "passive"))
    )
    (net (code "51") (name "Net-(M10-+)") (class "Default")
      (node (ref "M10") (pin "2") (pinfunction "+_2") (pintype "bidirectional"))
      (node (ref "R20") (pin "2") (pinfunction "W_2") (pintype "passive"))
    )
    (net (code "52") (name "Net-(PA-P$1)") (class "Default")
      (node (ref "PA") (pin "1") (pinfunction "P$1_1") (pintype "bidirectional"))
      (node (ref "T1000") (pin "3") (pinfunction "P1_3") (pintype "passive"))
    )
    (net (code "53") (name "Net-(PB-P$1)") (class "Default")
      (node (ref "PB") (pin "1") (pinfunction "P$1_1") (pintype "bidirectional"))
      (node (ref "T1000") (pin "5") (pinfunction "P2_5") (pintype "passive"))
    )
    (net (code "54") (name "Net-(PF1-P$1)") (class "Default")
      (node (ref "PF1") (pin "1") (pinfunction "P$1_1") (pintype "bidirectional"))
      (node (ref "PRECT") (pin "1") (pinfunction "P$1_1") (pintype "bidirectional"))
      (node (ref "S3") (pin "1") (pinfunction "1_1") (pintype "passive"))
      (node (ref "S4") (pin "1") (pinfunction "1_1") (pintype "passive"))
      (node (ref "S5") (pin "1") (pinfunction "1_1") (pintype "passive"))
      (node (ref "S6") (pin "1") (pinfunction "1_1") (pintype "passive"))
    )
    (net (code "55") (name "Net-(Q1-D)") (class "Default")
      (node (ref "Q1") (pin "3") (pinfunction "D_3") (pintype "passive"))
      (node (ref "R1") (pin "1") (pinfunction "1_1") (pintype "passive"))
      (node (ref "R2") (pin "1") (pinfunction "1_1") (pintype "passive"))
    )
    (net (code "56") (name "Net-(Q2-D)") (class "Default")
      (node (ref "F1") (pin "2@1") (pinfunction "P$2_2@1") (pintype "bidirectional"))
      (node (ref "F1") (pin "2@2") (pinfunction "P$2_2@2") (pintype "bidirectional"))
      (node (ref "Q2") (pin "3") (pinfunction "D_3") (pintype "passive"))
      (node (ref "R1") (pin "2") (pinfunction "2_2") (pintype "passive"))
    )
    (net (code "57") (name "Net-(Q2-G)") (class "Default")
      (node (ref "D1") (pin "C") (pinfunction "C_C") (pintype "passive"))
      (node (ref "Q2") (pin "1") (pinfunction "G_1") (pintype "passive"))
      (node (ref "Q3") (pin "3") (pinfunction "C_3") (pintype "passive"))
      (node (ref "R2") (pin "2") (pinfunction "2_2") (pintype "passive"))
    )
    (net (code "58") (name "Net-(Q2-S)") (class "Default")
      (node (ref "D1") (pin "A") (pinfunction "A_A") (pintype "passive"))
      (node (ref "Q2") (pin "2") (pinfunction "S_2") (pintype "passive"))
      (node (ref "Q3") (pin "1") (pinfunction "B_1") (pintype "passive"))
      (node (ref "R3") (pin "1") (pinfunction "1_1") (pintype "passive"))
    )
    (net (code "59") (name "Net-(R12-Pad2)") (class "Default")
      (node (ref "R12") (pin "2") (pinfunction "2_2") (pintype "passive"))
      (node (ref "S5") (pin "2") (pinfunction "2_2") (pintype "passive"))
    )
    (net (code "60") (name "Net-(R16-Pad2)") (class "Default")
      (node (ref "R16") (pin "2") (pinfunction "2_2") (pintype "passive"))
      (node (ref "S10") (pin "2") (pinfunction "2_2") (pintype "passive"))
    )
    (net (code "61") (name "Net-(R19-W)") (class "Default")
      (node (ref "R19") (pin "2") (pinfunction "W_2") (pintype "passive"))
      (node (ref "T600") (pin "1") (pinfunction "S1_1") (pintype "passive"))
    )
    (net (code "62") (name "Net-(SA-P$1)") (class "Default")
      (node (ref "SA") (pin "1") (pinfunction "P$1_1") (pintype "bidirectional"))
      (node (ref "T600") (pin "3") (pinfunction "P1_3") (pintype "passive"))
    )
    (net (code "63") (name "Net-(SB-P$1)") (class "Default")
      (node (ref "SB") (pin "1") (pinfunction "P$1_1") (pintype "bidirectional"))
      (node (ref "T600") (pin "5") (pinfunction "P2_5") (pintype "passive"))
    )
    (net (code "64") (name "Net-(SF1-P$1)") (class "Default")
      (node (ref "S10") (pin "1") (pinfunction "1_1") (pintype "passive"))
      (node (ref "S11") (pin "1") (pinfunction "1_1") (pintype "passive"))
      (node (ref "S8") (pin "1") (pinfunction "1_1") (pintype "passive"))
      (node (ref "S9") (pin "1") (pinfunction "1_1") (pintype "passive"))
      (node (ref "SF1") (pin "1") (pinfunction "P$1_1") (pintype "bidirectional"))
      (node (ref "SRECT") (pin "1") (pinfunction "P$1_1") (pintype "bidirectional"))
    )
    (net (code "65") (name "Net-(T100-P1)") (class "Default")
      (node (ref "D4") (pin "C") (pinfunction "C_C") (pintype "bidirectional"))
      (node (ref "T100") (pin "3") (pinfunction "P1_3") (pintype "passive"))
    )
    (net (code "66") (name "Net-(T100-P2)") (class "Default")
      (node (ref "D5") (pin "C") (pinfunction "C_C") (pintype "bidirectional"))
      (node (ref "T100") (pin "5") (pinfunction "P2_5") (pintype "passive"))
    )
    (net (code "67") (name "TOADC") (class "Default")
      (node (ref "D2") (pin "C") (pinfunction "C_C") (pintype "passive"))
      (node (ref "R4") (pin "1") (pinfunction "1_1") (pintype "passive"))
      (node (ref "R5") (pin "2") (pinfunction "2_2") (pintype "passive"))
      (node (ref "U1") (pin "6") (pinfunction "-IN_6") (pintype "input"))
    )
    (net (code "68") (name "V+") (class "Default")
      (node (ref "U1") (pin "8") (pinfunction "V+_8") (pintype "power_in"))
    )
    (net (code "69") (name "V-") (class "Default")
      (node (ref "U1") (pin "4") (pinfunction "V-_4") (pintype "power_in"))
    )
    (net (code "70") (name "unconnected-(U1A-+IN-Pad3)") (class "Default")
      (node (ref "U1") (pin "3") (pinfunction "+IN_3") (pintype "input"))
    )
    (net (code "71") (name "unconnected-(U1A--IN-Pad2)") (class "Default")
      (node (ref "U1") (pin "2") (pinfunction "-IN_2") (pintype "input"))
    )
    (net (code "72") (name "unconnected-(U1A-OUT-Pad1)") (class "Default")
      (node (ref "U1") (pin "1") (pinfunction "OUT_1") (pintype "output"))
    )
  )
)
